# Top_Level.net
KiCad netlist of a schematic drawn in Altium Designer
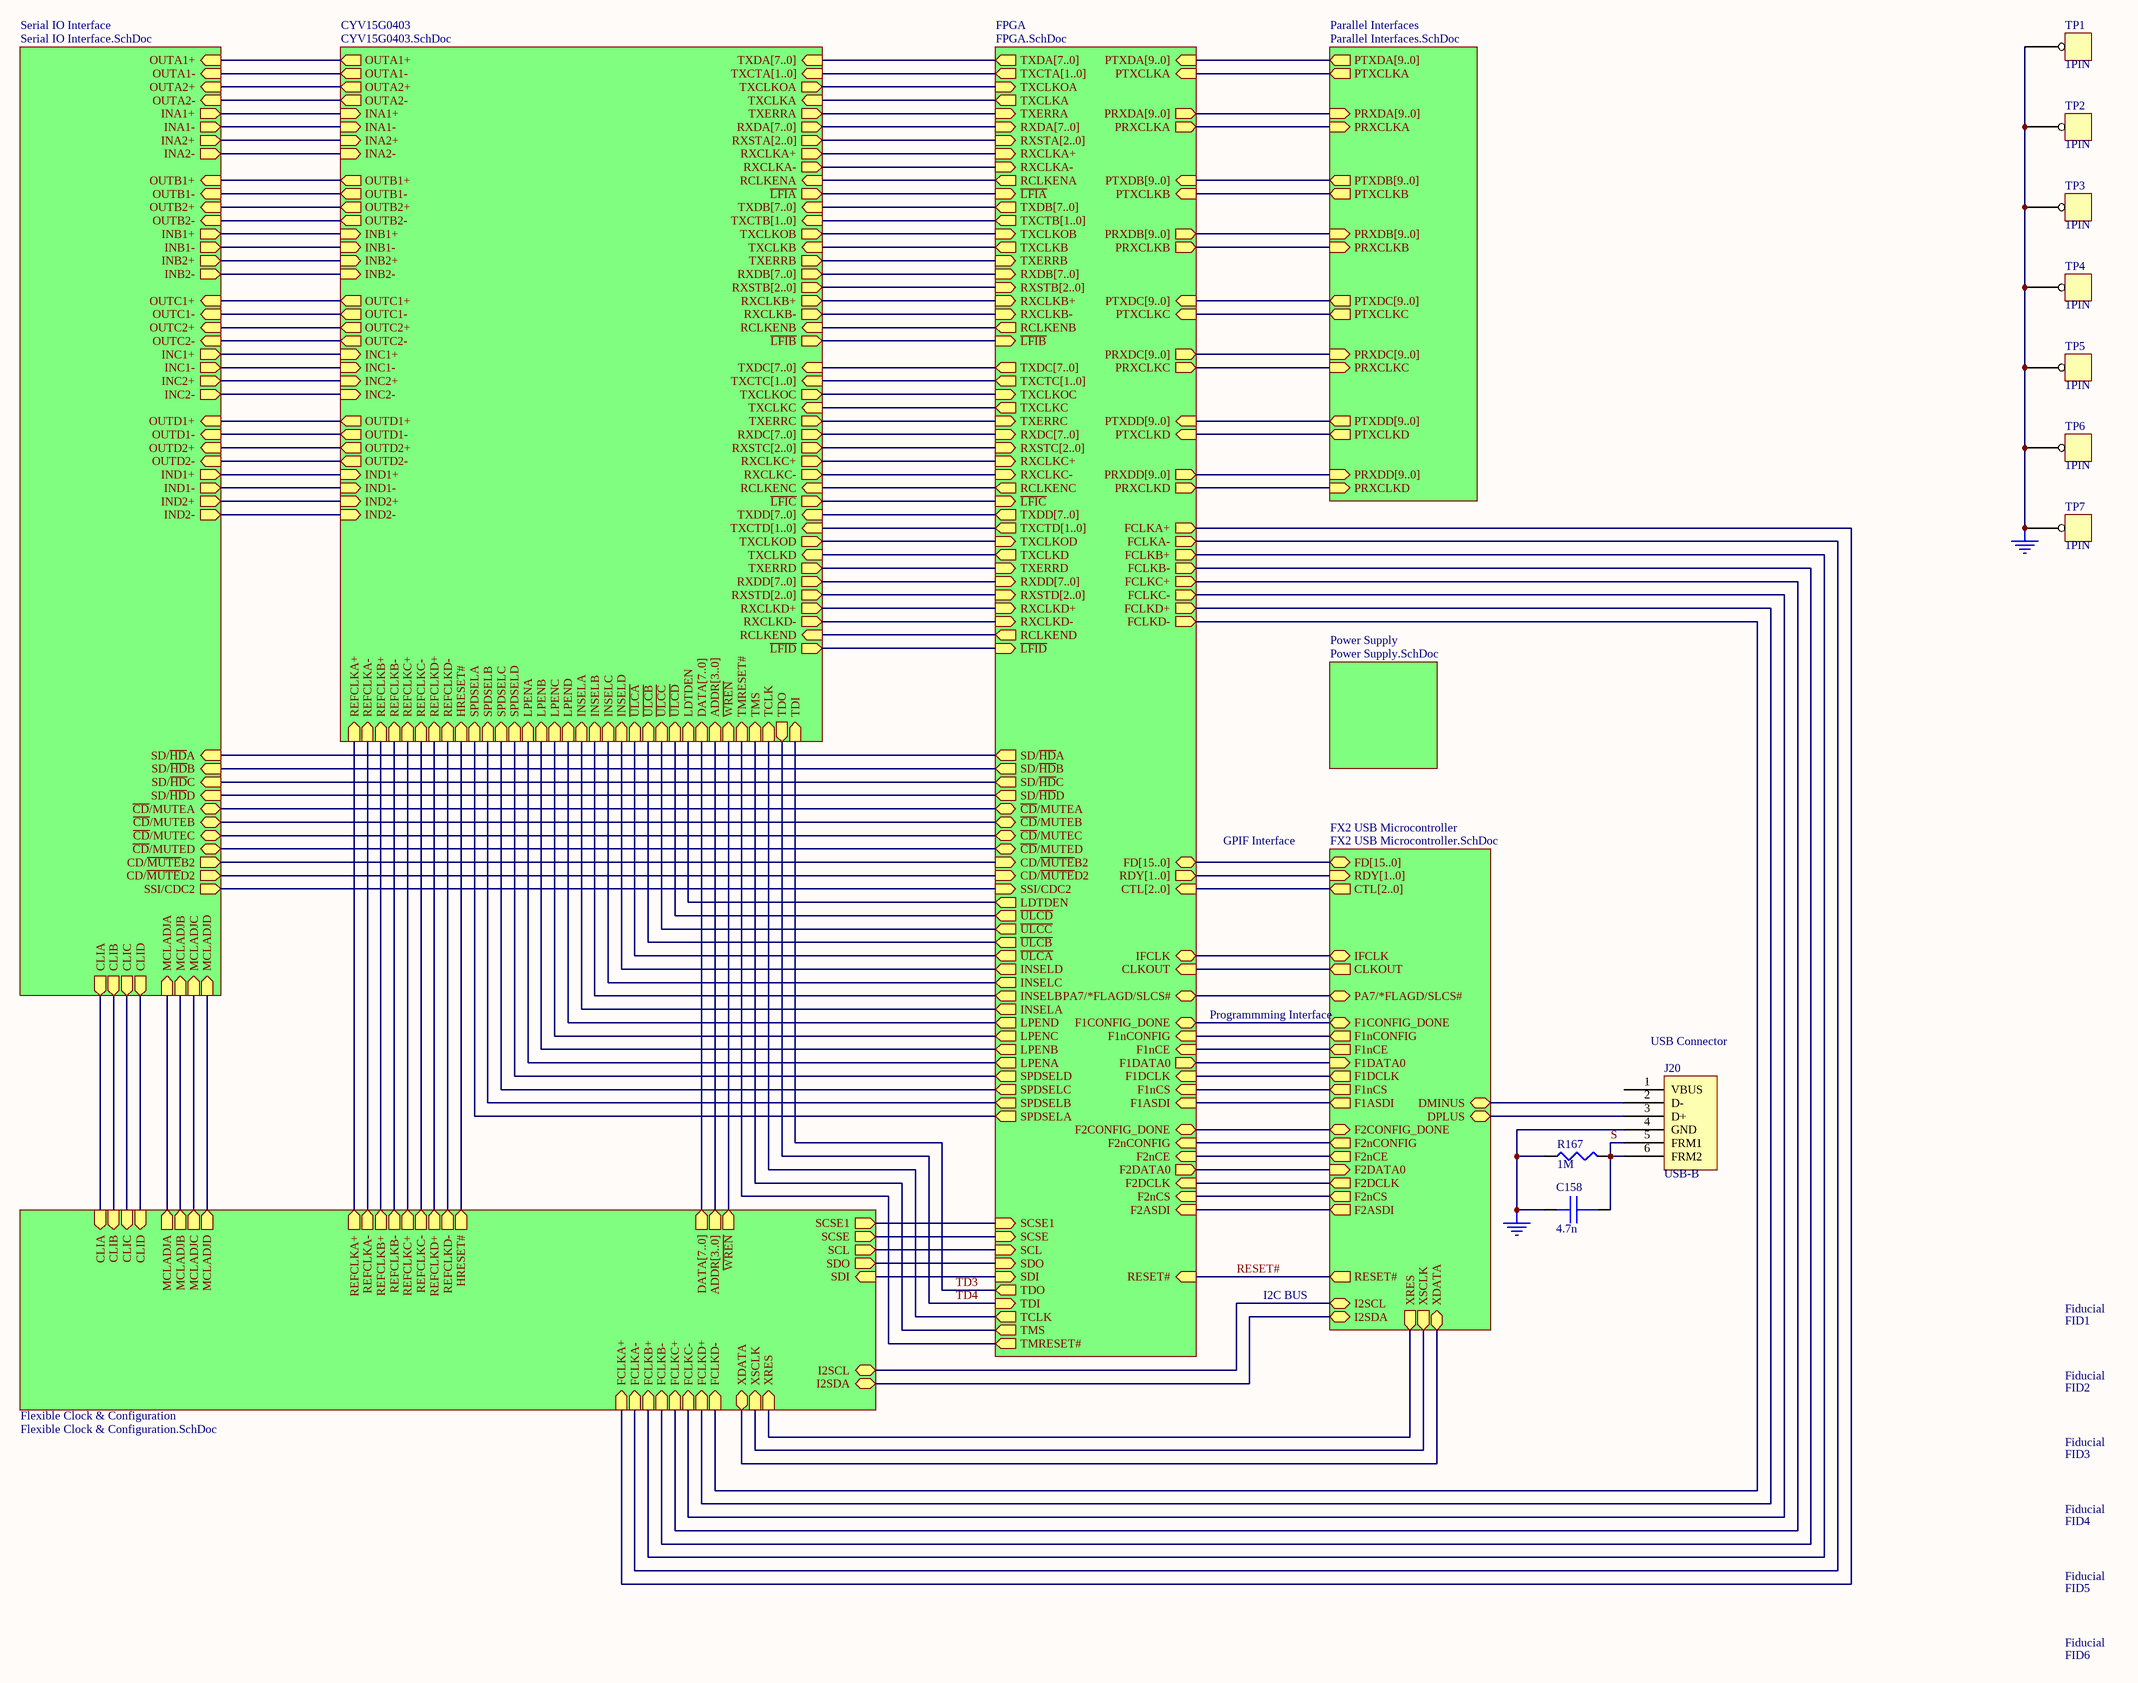
[diagram p0: Top Level.SchDoc]

(export (version "E")
  (design (tool "Eeschema 10.0.6"))
  (components
    (comp (ref "C158")
      (value "~")
      (footprint "0603")
      (description "SMT CAP")
      (libsource (lib "Cypress Molson") (part "CAP"))
    )
    (comp (ref "FID1")
      (value "FIDUCIAL")
      (footprint "FIDUCIAL")
      (description "Fiducial mark")
      (libsource (lib "Cypress Molson") (part "FIDUCIAL"))
    )
    (comp (ref "FID2")
      (value "FIDUCIAL")
      (footprint "FIDUCIAL")
      (description "Fiducial mark")
      (libsource (lib "Cypress Molson") (part "FIDUCIAL"))
    )
    (comp (ref "FID3")
      (value "FIDUCIAL")
      (footprint "FIDUCIAL")
      (description "Fiducial mark")
      (libsource (lib "Cypress Molson") (part "FIDUCIAL"))
    )
    (comp (ref "FID4")
      (value "FIDUCIAL")
      (footprint "FIDUCIAL")
      (description "Fiducial mark")
      (libsource (lib "Cypress Molson") (part "FIDUCIAL"))
    )
    (comp (ref "FID5")
      (value "FIDUCIAL")
      (footprint "FIDUCIAL")
      (description "Fiducial mark")
      (libsource (lib "Cypress Molson") (part "FIDUCIAL"))
    )
    (comp (ref "FID6")
      (value "FIDUCIAL")
      (footprint "FIDUCIAL")
      (description "Fiducial mark")
      (libsource (lib "Cypress Molson") (part "FIDUCIAL"))
    )
    (comp (ref "J20")
      (value "USB-B")
      (footprint "USB-B")
      (description "Universal Serial Bus Type B Receptacle")
      (libsource (lib "Schematic") (part "USB-B"))
    )
    (comp (ref "R167") (value "1M") (footprint "0603") (libsource (lib "Schematic") (part "RES1")))
    (comp (ref "TP1") (value "1PIN") (footprint "1PIN") (libsource (lib "Cypress Molson") (part "1PIN")))
    (comp (ref "TP2") (value "1PIN") (footprint "1PIN") (libsource (lib "Cypress Molson") (part "1PIN")))
    (comp (ref "TP3") (value "1PIN") (footprint "1PIN") (libsource (lib "Cypress Molson") (part "1PIN")))
    (comp (ref "TP4") (value "1PIN") (footprint "1PIN") (libsource (lib "Cypress Molson") (part "1PIN")))
    (comp (ref "TP5") (value "1PIN") (footprint "1PIN") (libsource (lib "Cypress Molson") (part "1PIN")))
    (comp (ref "TP6") (value "1PIN") (footprint "1PIN") (libsource (lib "Cypress Molson") (part "1PIN")))
    (comp (ref "TP7") (value "1PIN") (footprint "1PIN") (libsource (lib "Cypress Molson") (part "1PIN")))
  )
  (nets
    (net (code "11") (name "/DMINUS") (class "Default")
      (node (ref "J20") (pin "2") (pinfunction "D-_2") (pintype "passive"))
    )
    (net (code "12") (name "/DPLUS") (class "Default")
      (node (ref "J20") (pin "3") (pinfunction "D+_3") (pintype "passive"))
    )
    (net (code "132") (name "/S") (class "Default")
      (node (ref "C158") (pin "2") (pinfunction "2_2") (pintype "passive"))
      (node (ref "J20") (pin "5") (pinfunction "FRM1_5") (pintype "passive"))
      (node (ref "J20") (pin "6") (pinfunction "FRM2_6") (pintype "passive"))
      (node (ref "R167") (pin "2") (pintype "passive"))
    )
    (net (code "188") (name "GND") (class "Default")
      (node (ref "C158") (pin "1") (pinfunction "1_1") (pintype "passive"))
      (node (ref "J20") (pin "4") (pinfunction "GND_4") (pintype "power_in"))
      (node (ref "R167") (pin "1") (pintype "passive"))
      (node (ref "TP1") (pin "1") (pinfunction "1_1") (pintype "passive"))
      (node (ref "TP2") (pin "1") (pinfunction "1_1") (pintype "passive"))
      (node (ref "TP3") (pin "1") (pinfunction "1_1") (pintype "passive"))
      (node (ref "TP4") (pin "1") (pinfunction "1_1") (pintype "passive"))
      (node (ref "TP5") (pin "1") (pinfunction "1_1") (pintype "passive"))
      (node (ref "TP6") (pin "1") (pinfunction "1_1") (pintype "passive"))
      (node (ref "TP7") (pin "1") (pinfunction "1_1") (pintype "passive"))
    )
    (net (code "189") (name "unconnected-(J20-VBUS-Pad1)") (class "Default")
      (node (ref "J20") (pin "1") (pinfunction "VBUS_1") (pintype "power_in"))
    )
  )
)
